# Modulo_Servos.net
KiCad netlist of a schematic drawn in Altium Designer
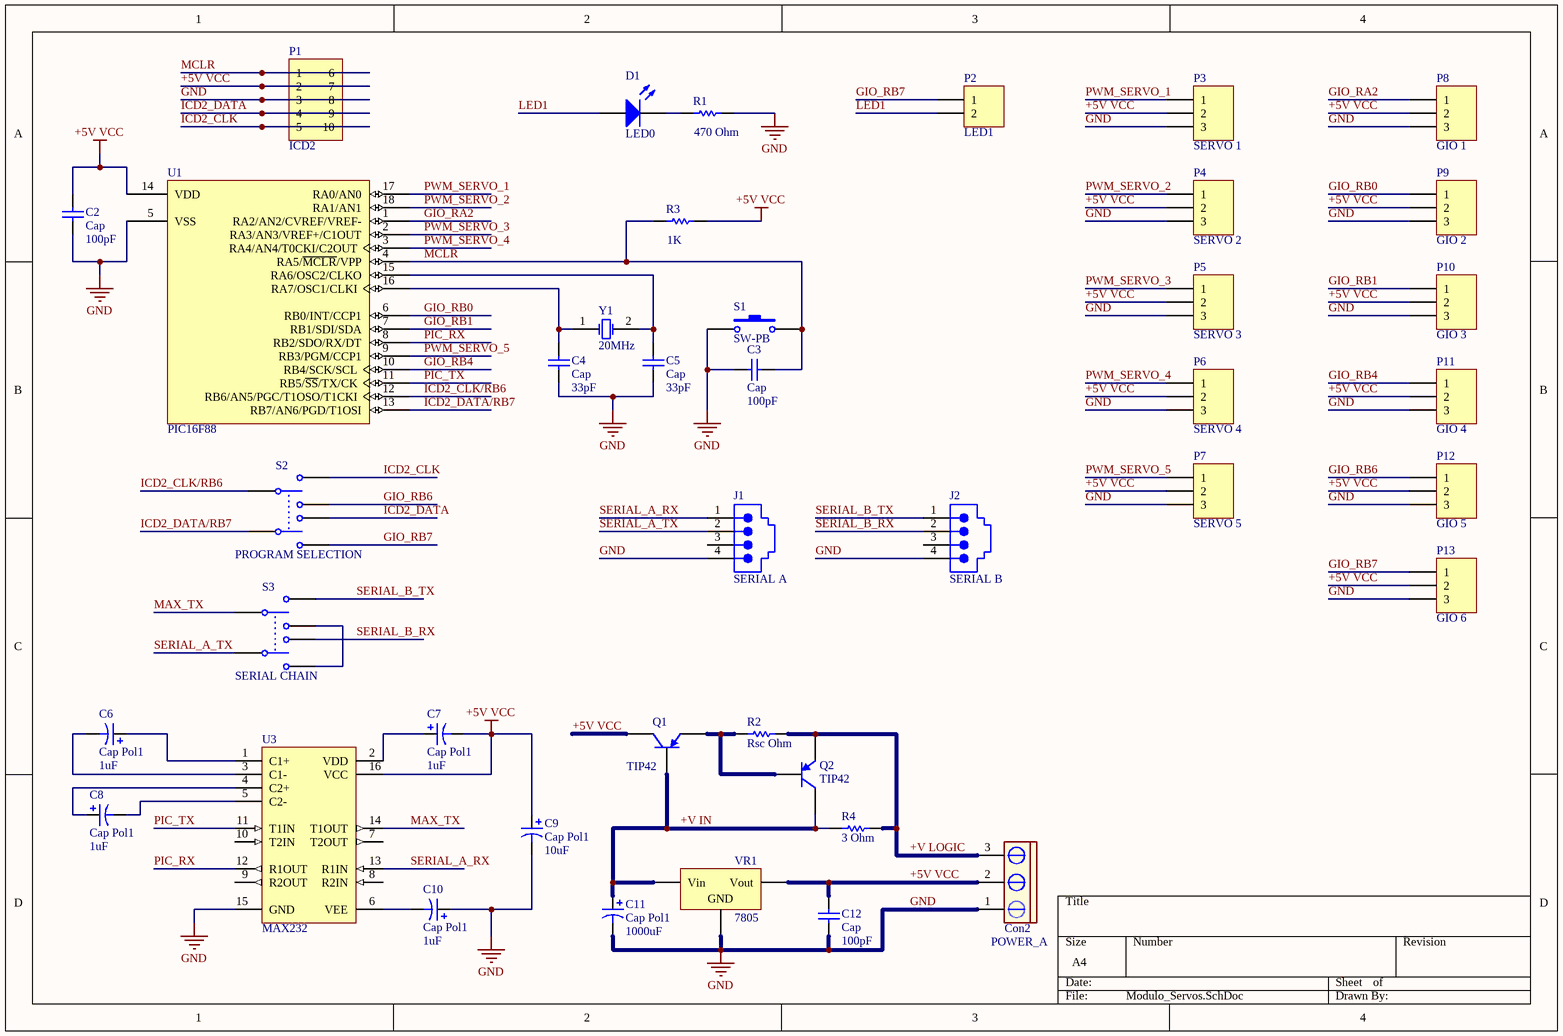
[diagram p0: Modulo_Servos.SchDoc]

(export (version "E")
  (design (tool "Eeschema 10.0.6"))
  (components
    (comp (ref "C2")
      (value "Cap")
      (footprint "CAPR2.54-5.1x3.2")
      (description "Capacitor")
      (fields (field (name "ALTIUM_VALUE") "100pF") (field (name "PUBLISHER") "Altium Limited"))
      (libsource (lib "Miscellaneous Devices") (part "Cap"))
    )
    (comp (ref "C3")
      (value "Cap")
      (footprint "CAPR2.54-5.1x3.2")
      (description "Capacitor")
      (fields (field (name "ALTIUM_VALUE") "100pF") (field (name "PUBLISHER") "Altium Limited"))
      (libsource (lib "Miscellaneous Devices") (part "Cap"))
    )
    (comp (ref "C4")
      (value "Cap")
      (footprint "CAPR2.54-5.1x3.2")
      (description "Capacitor")
      (fields (field (name "ALTIUM_VALUE") "33pF") (field (name "PUBLISHER") "Altium Limited"))
      (libsource (lib "Miscellaneous Devices") (part "Cap"))
    )
    (comp (ref "C5")
      (value "Cap")
      (footprint "CAPR2.54-5.1x3.2")
      (description "Capacitor")
      (fields (field (name "ALTIUM_VALUE") "33pF") (field (name "PUBLISHER") "Altium Limited"))
      (libsource (lib "Miscellaneous Devices") (part "Cap"))
    )
    (comp (ref "C6")
      (value "Cap Pol1")
      (footprint "CAPPR2-5x6.8")
      (description "Polarized Capacitor (Radial)")
      (fields (field (name "ALTIUM_VALUE") "1uF") (field (name "PUBLISHER") "Altium Limited"))
      (libsource (lib "Miscellaneous Devices") (part "Cap Pol1"))
    )
    (comp (ref "C7")
      (value "Cap Pol1")
      (footprint "CAPPR2-5x6.8")
      (description "Polarized Capacitor (Radial)")
      (fields (field (name "ALTIUM_VALUE") "1uF") (field (name "PUBLISHER") "Altium Limited"))
      (libsource (lib "Miscellaneous Devices") (part "Cap Pol1"))
    )
    (comp (ref "C8")
      (value "Cap Pol1")
      (footprint "CAPPR2-5x6.8")
      (description "Polarized Capacitor (Radial)")
      (fields (field (name "ALTIUM_VALUE") "1uF") (field (name "PUBLISHER") "Altium Limited"))
      (libsource (lib "Miscellaneous Devices") (part "Cap Pol1"))
    )
    (comp (ref "C9")
      (value "Cap Pol1")
      (footprint "CAPPR2-5x6.8")
      (description "Polarized Capacitor (Radial)")
      (fields (field (name "ALTIUM_VALUE") "10uF") (field (name "PUBLISHER") "Altium Limited"))
      (libsource (lib "Miscellaneous Devices") (part "Cap Pol1"))
    )
    (comp (ref "C10")
      (value "Cap Pol1")
      (footprint "CAPPR2-5x6.8")
      (description "Polarized Capacitor (Radial)")
      (fields (field (name "ALTIUM_VALUE") "1uF") (field (name "PUBLISHER") "Altium Limited"))
      (libsource (lib "Miscellaneous Devices") (part "Cap Pol1"))
    )
    (comp (ref "C11")
      (value "Cap Pol1")
      (footprint "RB5-10.5")
      (description "Polarized Capacitor (Radial)")
      (fields (field (name "ALTIUM_VALUE") "1000uF") (field (name "PUBLISHER") "Altium Limited"))
      (libsource (lib "Miscellaneous Devices") (part "Cap Pol1"))
    )
    (comp (ref "C12")
      (value "Cap")
      (footprint "CAPR2.54-5.1x3.2")
      (description "Capacitor")
      (fields (field (name "ALTIUM_VALUE") "100pF") (field (name "PUBLISHER") "Altium Limited"))
      (libsource (lib "Miscellaneous Devices") (part "Cap"))
    )
    (comp (ref "Con2")
      (value "POWER_A")
      (footprint "My_CN3")
      (description "Connector green screw")
      (libsource (lib "Protel_Library") (part "CON3 pin Green"))
    )
    (comp (ref "D1")
      (value "LED0")
      (footprint "LED-0")
      (description "Typical INFRARED GaAs LED")
      (fields (field (name "PUBLISHER") "Altium Limited"))
      (libsource (lib "Miscellaneous Devices") (part "LED0"))
    )
    (comp (ref "J1")
      (value "SERIAL A")
      (footprint "15-43-6245")
      (description "Right Angle, Standard Profile, RJ45-Keyed, Flange Mount PCB Jack")
      (fields (field (name "PUBLISHER") "Altium Limited"))
      (libsource (lib "Molex Modular Jack Right Angle") (part "15-43-6245"))
    )
    (comp (ref "J2")
      (value "SERIAL B")
      (footprint "15-43-6245")
      (description "Right Angle, Standard Profile, RJ45-Keyed, Flange Mount PCB Jack")
      (fields (field (name "PUBLISHER") "Altium Limited"))
      (libsource (lib "Molex Modular Jack Right Angle") (part "15-43-6245"))
    )
    (comp (ref "P1")
      (value "ICD2")
      (footprint "HEADER10_5x2_B")
      (description "Header, 5-Pin, Dual row")
      (fields (field (name "PUBLISHER") "Altium Limited"))
      (libsource (lib "Miscellaneous Connectors") (part "Header 5X2A"))
    )
    (comp (ref "P2")
      (value "LED1")
      (footprint "HDR1X2")
      (description "Header, 2-Pin")
      (fields (field (name "PUBLISHER") "Altium Limited"))
      (libsource (lib "Miscellaneous Connectors") (part "Header 2"))
    )
    (comp (ref "P3")
      (value "SERVO 1")
      (footprint "HDR1X3")
      (description "Header, 3-Pin")
      (fields (field (name "PUBLISHER") "Altium Limited"))
      (libsource (lib "Miscellaneous Connectors") (part "Header 3"))
    )
    (comp (ref "P4")
      (value "SERVO 2")
      (footprint "HDR1X3")
      (description "Header, 3-Pin")
      (fields (field (name "PUBLISHER") "Altium Limited"))
      (libsource (lib "Miscellaneous Connectors") (part "Header 3"))
    )
    (comp (ref "P5")
      (value "SERVO 3")
      (footprint "HDR1X3")
      (description "Header, 3-Pin")
      (fields (field (name "PUBLISHER") "Altium Limited"))
      (libsource (lib "Miscellaneous Connectors") (part "Header 3"))
    )
    (comp (ref "P6")
      (value "SERVO 4")
      (footprint "HDR1X3")
      (description "Header, 3-Pin")
      (fields (field (name "PUBLISHER") "Altium Limited"))
      (libsource (lib "Miscellaneous Connectors") (part "Header 3"))
    )
    (comp (ref "P7")
      (value "SERVO 5")
      (footprint "HDR1X3")
      (description "Header, 3-Pin")
      (fields (field (name "PUBLISHER") "Altium Limited"))
      (libsource (lib "Miscellaneous Connectors") (part "Header 3"))
    )
    (comp (ref "P8")
      (value "GIO 1")
      (footprint "HDR1X3")
      (description "Header, 3-Pin")
      (fields (field (name "PUBLISHER") "Altium Limited"))
      (libsource (lib "Miscellaneous Connectors") (part "Header 3"))
    )
    (comp (ref "P9")
      (value "GIO 2")
      (footprint "HDR1X3")
      (description "Header, 3-Pin")
      (fields (field (name "PUBLISHER") "Altium Limited"))
      (libsource (lib "Miscellaneous Connectors") (part "Header 3"))
    )
    (comp (ref "P10")
      (value "GIO 3")
      (footprint "HDR1X3")
      (description "Header, 3-Pin")
      (fields (field (name "PUBLISHER") "Altium Limited"))
      (libsource (lib "Miscellaneous Connectors") (part "Header 3"))
    )
    (comp (ref "P11")
      (value "GIO 4")
      (footprint "HDR1X3")
      (description "Header, 3-Pin")
      (fields (field (name "PUBLISHER") "Altium Limited"))
      (libsource (lib "Miscellaneous Connectors") (part "Header 3"))
    )
    (comp (ref "P12")
      (value "GIO 5")
      (footprint "HDR1X3")
      (description "Header, 3-Pin")
      (fields (field (name "PUBLISHER") "Altium Limited"))
      (libsource (lib "Miscellaneous Connectors") (part "Header 3"))
    )
    (comp (ref "P13")
      (value "GIO 6")
      (footprint "HDR1X3")
      (description "Header, 3-Pin")
      (fields (field (name "PUBLISHER") "Altium Limited"))
      (libsource (lib "Miscellaneous Connectors") (part "Header 3"))
    )
    (comp (ref "Q1")
      (value "TIP42")
      (footprint "TO-220")
      (description "PNP Power Amplifier")
      (fields (field (name "PUBLISHER") "Altium Limited"))
      (libsource (lib "FSC Discrete BJT") (part "D45H8"))
    )
    (comp (ref "Q2")
      (value "TIP42")
      (footprint "TO-220")
      (description "PNP Power Amplifier")
      (fields (field (name "PUBLISHER") "Altium Limited"))
      (libsource (lib "") (part "D45H8_1"))
    )
    (comp (ref "R1")
      (value "470 Ohm")
      (footprint "AXIAL-0.3")
      (description "Resistor")
      (fields (field (name "Comment") "Res1") (field (name "PUBLISHER") "Altium Limited"))
      (libsource (lib "Miscellaneous Devices") (part "Res1"))
    )
    (comp (ref "R2")
      (value "Rsc Ohm")
      (footprint "AXIAL-0.3")
      (description "Resistor")
      (fields (field (name "Comment") "Res1") (field (name "PUBLISHER") "Altium Limited"))
      (libsource (lib "Miscellaneous Devices") (part "Res1"))
    )
    (comp (ref "R3")
      (value "1K")
      (footprint "AXIAL-0.3")
      (description "Resistor")
      (fields (field (name "Comment") "Res1") (field (name "PUBLISHER") "Altium Limited"))
      (libsource (lib "Miscellaneous Devices") (part "Res1"))
    )
    (comp (ref "R4")
      (value "3 Ohm")
      (footprint "AXIAL-0.3")
      (description "Resistor")
      (fields (field (name "Comment") "Res1") (field (name "PUBLISHER") "Altium Limited"))
      (libsource (lib "Miscellaneous Devices") (part "Res1"))
    )
    (comp (ref "S1")
      (value "SW-PB")
      (footprint "TS-063")
      (description "Switch")
      (fields (field (name "PUBLISHER") "Altium Limited"))
      (libsource (lib "Miscellaneous Devices") (part "SW-PB"))
    )
    (comp (ref "S2")
      (value "PROGRAM SELECTION")
      (footprint "LD-202mini")
      (description "Double-Pole, Double-Throw Switch")
      (fields (field (name "PUBLISHER") "Altium Limited"))
      (libsource (lib "Miscellaneous Devices") (part "SW-DPDT"))
    )
    (comp (ref "S3")
      (value "SERIAL CHAIN")
      (footprint "LD-202mini")
      (description "Double-Pole, Double-Throw Switch")
      (fields (field (name "PUBLISHER") "Altium Limited"))
      (libsource (lib "Miscellaneous Devices") (part "SW-DPDT"))
    )
    (comp (ref "U1")
      (value "PIC16F88")
      (footprint "PDIP300-P18")
      (fields (field (name "PUBLISHER") "Altium Limited"))
      (libsource (lib "Microchip Microcontroller 8-Bit PIC16") (part "PIC16F88-E/P"))
    )
    (comp (ref "U3")
      (value "MAX232")
      (footprint "PE16A")
      (description "+5V Powered, Multi-Channel RS-232 Driver/Receiver")
      (fields (field (name "PUBLISHER") "Altium Limited"))
      (libsource (lib "Maxim Communication Transceiver") (part "MAX232ACPE"))
    )
    (comp (ref "VR1")
      (value "7805")
      (footprint "TO-220")
      (description "Voltage Regulator")
      (fields (field (name "PUBLISHER") "Altium Limited"))
      (libsource (lib "Miscellaneous Devices") (part "Volt Reg"))
    )
    (comp (ref "Y1")
      (value "20MHz")
      (footprint "My_Crystal")
      (description "Crystal Oscillator")
      (fields (field (name "PUBLISHER") "Altium Limited"))
      (libsource (lib "Miscellaneous Devices") (part "XTAL"))
    )
  )
  (nets
    (net (code "1") (name "+5V VCC") (class "Default")
      (node (ref "C12") (pin "2") (pinfunction "2_2") (pintype "passive"))
      (node (ref "C2") (pin "2") (pinfunction "2_2") (pintype "passive"))
      (node (ref "C7") (pin "2") (pinfunction "2_2") (pintype "passive"))
      (node (ref "C9") (pin "1") (pinfunction "1_1") (pintype "passive"))
      (node (ref "Con2") (pin "2") (pinfunction "2_2") (pintype "passive"))
      (node (ref "P1") (pin "2") (pinfunction "2_2") (pintype "passive"))
      (node (ref "P1") (pin "7") (pinfunction "7_7") (pintype "passive"))
      (node (ref "P10") (pin "2") (pinfunction "2_2") (pintype "passive"))
      (node (ref "P11") (pin "2") (pinfunction "2_2") (pintype "passive"))
      (node (ref "P12") (pin "2") (pinfunction "2_2") (pintype "passive"))
      (node (ref "P13") (pin "2") (pinfunction "2_2") (pintype "passive"))
      (node (ref "P3") (pin "2") (pinfunction "2_2") (pintype "passive"))
      (node (ref "P4") (pin "2") (pinfunction "2_2") (pintype "passive"))
      (node (ref "P5") (pin "2") (pinfunction "2_2") (pintype "passive"))
      (node (ref "P6") (pin "2") (pinfunction "2_2") (pintype "passive"))
      (node (ref "P7") (pin "2") (pinfunction "2_2") (pintype "passive"))
      (node (ref "P8") (pin "2") (pinfunction "2_2") (pintype "passive"))
      (node (ref "P9") (pin "2") (pinfunction "2_2") (pintype "passive"))
      (node (ref "Q1") (pin "2") (pinfunction "C_2") (pintype "passive"))
      (node (ref "R3") (pin "2") (pinfunction "2_2") (pintype "passive"))
      (node (ref "U1") (pin "14") (pinfunction "VDD_14") (pintype "power_in"))
      (node (ref "U3") (pin "16") (pinfunction "VCC_16") (pintype "power_in"))
      (node (ref "VR1") (pin "3") (pinfunction "Vout_3") (pintype "passive"))
    )
    (net (code "2") (name "/+V IN") (class "Default")
      (node (ref "C11") (pin "1") (pinfunction "1_1") (pintype "passive"))
      (node (ref "Q1") (pin "1") (pinfunction "B_1") (pintype "passive"))
      (node (ref "Q2") (pin "2") (pinfunction "C_2") (pintype "passive"))
      (node (ref "R4") (pin "2") (pinfunction "2_2") (pintype "passive"))
      (node (ref "VR1") (pin "1") (pinfunction "Vin_1") (pintype "passive"))
    )
    (net (code "3") (name "/+V LOGIC") (class "Default")
      (node (ref "Con2") (pin "3") (pinfunction "3_3") (pintype "passive"))
      (node (ref "Q2") (pin "3") (pinfunction "E_3") (pintype "passive"))
      (node (ref "R2") (pin "1") (pinfunction "1_1") (pintype "passive"))
      (node (ref "R4") (pin "1") (pinfunction "1_1") (pintype "passive"))
    )
    (net (code "4") (name "/GIO_RA2") (class "Default")
      (node (ref "P8") (pin "1") (pinfunction "1_1") (pintype "passive"))
      (node (ref "U1") (pin "1") (pinfunction "RA2/AN2/CVREF/VREF-_1") (pintype "bidirectional"))
    )
    (net (code "5") (name "/GIO_RB0") (class "Default")
      (node (ref "P9") (pin "1") (pinfunction "1_1") (pintype "passive"))
      (node (ref "U1") (pin "6") (pinfunction "RB0/INT/CCP1_6") (pintype "bidirectional"))
    )
    (net (code "6") (name "/GIO_RB1") (class "Default")
      (node (ref "P10") (pin "1") (pinfunction "1_1") (pintype "passive"))
      (node (ref "U1") (pin "7") (pinfunction "RB1/SDI/SDA_7") (pintype "bidirectional"))
    )
    (net (code "7") (name "/GIO_RB4") (class "Default")
      (node (ref "P11") (pin "1") (pinfunction "1_1") (pintype "passive"))
      (node (ref "U1") (pin "10") (pinfunction "RB4/SCK/SCL_10") (pintype "bidirectional"))
    )
    (net (code "8") (name "/GIO_RB6") (class "Default")
      (node (ref "P12") (pin "1") (pinfunction "1_1") (pintype "passive"))
      (node (ref "S2") (pin "3") (pinfunction "3_3") (pintype "passive"))
    )
    (net (code "9") (name "/GIO_RB7") (class "Default")
      (node (ref "P13") (pin "1") (pinfunction "1_1") (pintype "passive"))
      (node (ref "P2") (pin "1") (pinfunction "1_1") (pintype "passive"))
      (node (ref "S2") (pin "6") (pinfunction "6_6") (pintype "passive"))
    )
    (net (code "10") (name "/ICD2_CLK") (class "Default")
      (node (ref "P1") (pin "10") (pinfunction "10_10") (pintype "passive"))
      (node (ref "P1") (pin "5") (pinfunction "5_5") (pintype "passive"))
      (node (ref "S2") (pin "2") (pinfunction "2_2") (pintype "passive"))
    )
    (net (code "11") (name "/ICD2_CLK{slash}RB6") (class "Default")
      (node (ref "S2") (pin "1") (pinfunction "1_1") (pintype "passive"))
      (node (ref "U1") (pin "12") (pinfunction "RB6/AN5/PGC/T1OSO/T1CKI_12") (pintype "bidirectional"))
    )
    (net (code "12") (name "/ICD2_DATA") (class "Default")
      (node (ref "P1") (pin "4") (pinfunction "4_4") (pintype "passive"))
      (node (ref "P1") (pin "9") (pinfunction "9_9") (pintype "passive"))
      (node (ref "S2") (pin "5") (pinfunction "5_5") (pintype "passive"))
    )
    (net (code "13") (name "/ICD2_DATA{slash}RB7") (class "Default")
      (node (ref "S2") (pin "4") (pinfunction "4_4") (pintype "passive"))
      (node (ref "U1") (pin "13") (pinfunction "RB7/AN6/PGD/T1OSI_13") (pintype "bidirectional"))
    )
    (net (code "14") (name "/LED1") (class "Default")
      (node (ref "D1") (pin "1") (pinfunction "A_1") (pintype "passive"))
      (node (ref "P2") (pin "2") (pinfunction "2_2") (pintype "passive"))
    )
    (net (code "15") (name "/MAX_TX") (class "Default")
      (node (ref "S3") (pin "1") (pinfunction "1_1") (pintype "passive"))
      (node (ref "U3") (pin "14") (pinfunction "T1OUT_14") (pintype "output"))
    )
    (net (code "16") (name "/MCLR") (class "Default")
      (node (ref "C3") (pin "2") (pinfunction "2_2") (pintype "passive"))
      (node (ref "P1") (pin "1") (pinfunction "1_1") (pintype "passive"))
      (node (ref "P1") (pin "6") (pinfunction "6_6") (pintype "passive"))
      (node (ref "R3") (pin "1") (pinfunction "1_1") (pintype "passive"))
      (node (ref "S1") (pin "2") (pinfunction "2_2") (pintype "passive"))
      (node (ref "U1") (pin "4") (pinfunction "RA5/~{MCLR}/VPP_4") (pintype "bidirectional"))
    )
    (net (code "17") (name "/PIC_RX") (class "Default")
      (node (ref "U1") (pin "8") (pinfunction "RB2/SDO/RX/DT_8") (pintype "bidirectional"))
      (node (ref "U3") (pin "12") (pinfunction "R1OUT_12") (pintype "output"))
    )
    (net (code "18") (name "/PIC_TX") (class "Default")
      (node (ref "U1") (pin "11") (pinfunction "RB5/~{SS}/TX/CK_11") (pintype "bidirectional"))
      (node (ref "U3") (pin "11") (pinfunction "T1IN_11") (pintype "input"))
    )
    (net (code "19") (name "/PWM_SERVO_1") (class "Default")
      (node (ref "P3") (pin "1") (pinfunction "1_1") (pintype "passive"))
      (node (ref "U1") (pin "17") (pinfunction "RA0/AN0_17") (pintype "bidirectional"))
    )
    (net (code "20") (name "/PWM_SERVO_2") (class "Default")
      (node (ref "P4") (pin "1") (pinfunction "1_1") (pintype "passive"))
      (node (ref "U1") (pin "18") (pinfunction "RA1/AN1_18") (pintype "bidirectional"))
    )
    (net (code "21") (name "/PWM_SERVO_3") (class "Default")
      (node (ref "P5") (pin "1") (pinfunction "1_1") (pintype "passive"))
      (node (ref "U1") (pin "2") (pinfunction "RA3/AN3/VREF+/C1OUT_2") (pintype "bidirectional"))
    )
    (net (code "22") (name "/PWM_SERVO_4") (class "Default")
      (node (ref "P6") (pin "1") (pinfunction "1_1") (pintype "passive"))
      (node (ref "U1") (pin "3") (pinfunction "RA4/AN4/T0CKI/C2OUT_3") (pintype "bidirectional"))
    )
    (net (code "23") (name "/PWM_SERVO_5") (class "Default")
      (node (ref "P7") (pin "1") (pinfunction "1_1") (pintype "passive"))
      (node (ref "U1") (pin "9") (pinfunction "RB3/PGM/CCP1_9") (pintype "bidirectional"))
    )
    (net (code "24") (name "/SERIAL_A_RX") (class "Default")
      (node (ref "J1") (pin "1") (pinfunction "1_1") (pintype "passive"))
      (node (ref "U3") (pin "13") (pinfunction "R1IN_13") (pintype "input"))
    )
    (net (code "25") (name "/SERIAL_A_TX") (class "Default")
      (node (ref "J1") (pin "2") (pinfunction "2_2") (pintype "passive"))
      (node (ref "S3") (pin "4") (pinfunction "4_4") (pintype "passive"))
    )
    (net (code "26") (name "/SERIAL_B_RX") (class "Default")
      (node (ref "J2") (pin "2") (pinfunction "2_2") (pintype "passive"))
      (node (ref "S3") (pin "5") (pinfunction "5_5") (pintype "passive"))
    )
    (net (code "27") (name "/SERIAL_B_TX") (class "Default")
      (node (ref "J2") (pin "1") (pinfunction "1_1") (pintype "passive"))
      (node (ref "S3") (pin "2") (pinfunction "2_2") (pintype "passive"))
    )
    (net (code "28") (name "GND") (class "Default")
      (node (ref "C10") (pin "1") (pinfunction "1_1") (pintype "passive"))
      (node (ref "C11") (pin "2") (pinfunction "2_2") (pintype "passive"))
      (node (ref "C12") (pin "1") (pinfunction "1_1") (pintype "passive"))
      (node (ref "C2") (pin "1") (pinfunction "1_1") (pintype "passive"))
      (node (ref "C3") (pin "1") (pinfunction "1_1") (pintype "passive"))
      (node (ref "C4") (pin "1") (pinfunction "1_1") (pintype "passive"))
      (node (ref "C5") (pin "1") (pinfunction "1_1") (pintype "passive"))
      (node (ref "C9") (pin "2") (pinfunction "2_2") (pintype "passive"))
      (node (ref "Con2") (pin "1") (pinfunction "1_1") (pintype "passive"))
      (node (ref "J1") (pin "4") (pinfunction "4_4") (pintype "passive"))
      (node (ref "J2") (pin "4") (pinfunction "4_4") (pintype "passive"))
      (node (ref "P1") (pin "3") (pinfunction "3_3") (pintype "passive"))
      (node (ref "P1") (pin "8") (pinfunction "8_8") (pintype "passive"))
      (node (ref "P10") (pin "3") (pinfunction "3_3") (pintype "passive"))
      (node (ref "P11") (pin "3") (pinfunction "3_3") (pintype "passive"))
      (node (ref "P12") (pin "3") (pinfunction "3_3") (pintype "passive"))
      (node (ref "P13") (pin "3") (pinfunction "3_3") (pintype "passive"))
      (node (ref "P3") (pin "3") (pinfunction "3_3") (pintype "passive"))
      (node (ref "P4") (pin "3") (pinfunction "3_3") (pintype "passive"))
      (node (ref "P5") (pin "3") (pinfunction "3_3") (pintype "passive"))
      (node (ref "P6") (pin "3") (pinfunction "3_3") (pintype "passive"))
      (node (ref "P7") (pin "3") (pinfunction "3_3") (pintype "passive"))
      (node (ref "P8") (pin "3") (pinfunction "3_3") (pintype "passive"))
      (node (ref "P9") (pin "3") (pinfunction "3_3") (pintype "passive"))
      (node (ref "R1") (pin "2") (pinfunction "2_2") (pintype "passive"))
      (node (ref "S1") (pin "1") (pinfunction "1_1") (pintype "passive"))
      (node (ref "U1") (pin "5") (pinfunction "VSS_5") (pintype "power_in"))
      (node (ref "U3") (pin "15") (pinfunction "GND_15") (pintype "power_in"))
      (node (ref "VR1") (pin "2") (pinfunction "GND_2") (pintype "passive"))
    )
    (net (code "29") (name "Net-(D1-K)") (class "Default")
      (node (ref "D1") (pin "2") (pinfunction "K_2") (pintype "passive"))
      (node (ref "R1") (pin "1") (pinfunction "1_1") (pintype "passive"))
    )
    (net (code "30") (name "Net-(Q1-E)") (class "Default")
      (node (ref "Q1") (pin "3") (pinfunction "E_3") (pintype "passive"))
      (node (ref "Q2") (pin "1") (pinfunction "B_1") (pintype "passive"))
      (node (ref "R2") (pin "2") (pinfunction "2_2") (pintype "passive"))
    )
    (net (code "31") (name "Net-(S3-Pad3)") (class "Default")
      (node (ref "S3") (pin "3") (pinfunction "3_3") (pintype "passive"))
      (node (ref "S3") (pin "6") (pinfunction "6_6") (pintype "passive"))
    )
    (net (code "32") (name "Net-(U1-RA6{slash}OSC2{slash}CLKO)") (class "Default")
      (node (ref "C5") (pin "2") (pinfunction "2_2") (pintype "passive"))
      (node (ref "U1") (pin "15") (pinfunction "RA6/OSC2/CLKO_15") (pintype "bidirectional"))
      (node (ref "Y1") (pin "2") (pinfunction "OSC2_2") (pintype "passive"))
    )
    (net (code "33") (name "Net-(U1-RA7{slash}OSC1{slash}CLKI)") (class "Default")
      (node (ref "C4") (pin "2") (pinfunction "2_2") (pintype "passive"))
      (node (ref "U1") (pin "16") (pinfunction "RA7/OSC1/CLKI_16") (pintype "bidirectional"))
      (node (ref "Y1") (pin "1") (pinfunction "OSC1_1") (pintype "passive"))
    )
    (net (code "34") (name "Net-(U3-C1+)") (class "Default")
      (node (ref "C6") (pin "1") (pinfunction "1_1") (pintype "passive"))
      (node (ref "U3") (pin "1") (pinfunction "C1+_1") (pintype "passive"))
    )
    (net (code "35") (name "Net-(U3-C1-)") (class "Default")
      (node (ref "C6") (pin "2") (pinfunction "2_2") (pintype "passive"))
      (node (ref "U3") (pin "3") (pinfunction "C1-_3") (pintype "passive"))
    )
    (net (code "36") (name "Net-(U3-C2+)") (class "Default")
      (node (ref "C8") (pin "1") (pinfunction "1_1") (pintype "passive"))
      (node (ref "U3") (pin "4") (pinfunction "C2+_4") (pintype "passive"))
    )
    (net (code "37") (name "Net-(U3-C2-)") (class "Default")
      (node (ref "C8") (pin "2") (pinfunction "2_2") (pintype "passive"))
      (node (ref "U3") (pin "5") (pinfunction "C2-_5") (pintype "passive"))
    )
    (net (code "38") (name "Net-(U3-VDD)") (class "Default")
      (node (ref "C7") (pin "1") (pinfunction "1_1") (pintype "passive"))
      (node (ref "U3") (pin "2") (pinfunction "VDD_2") (pintype "power_in"))
    )
    (net (code "39") (name "Net-(U3-VEE)") (class "Default")
      (node (ref "C10") (pin "2") (pinfunction "2_2") (pintype "passive"))
      (node (ref "U3") (pin "6") (pinfunction "VEE_6") (pintype "power_in"))
    )
    (net (code "40") (name "unconnected-(J1-Pad3)") (class "Default")
      (node (ref "J1") (pin "3") (pinfunction "3_3") (pintype "passive"))
    )
    (net (code "41") (name "unconnected-(J2-Pad3)") (class "Default")
      (node (ref "J2") (pin "3") (pinfunction "3_3") (pintype "passive"))
    )
    (net (code "42") (name "unconnected-(U3-R2IN-Pad8)") (class "Default")
      (node (ref "U3") (pin "8") (pinfunction "R2IN_8") (pintype "input"))
    )
    (net (code "43") (name "unconnected-(U3-R2OUT-Pad9)") (class "Default")
      (node (ref "U3") (pin "9") (pinfunction "R2OUT_9") (pintype "output"))
    )
    (net (code "44") (name "unconnected-(U3-T2IN-Pad10)") (class "Default")
      (node (ref "U3") (pin "10") (pinfunction "T2IN_10") (pintype "input"))
    )
    (net (code "45") (name "unconnected-(U3-T2OUT-Pad7)") (class "Default")
      (node (ref "U3") (pin "7") (pinfunction "T2OUT_7") (pintype "output"))
    )
  )
)
